# filter.net
KiCad netlist of a schematic drawn in EAGLE
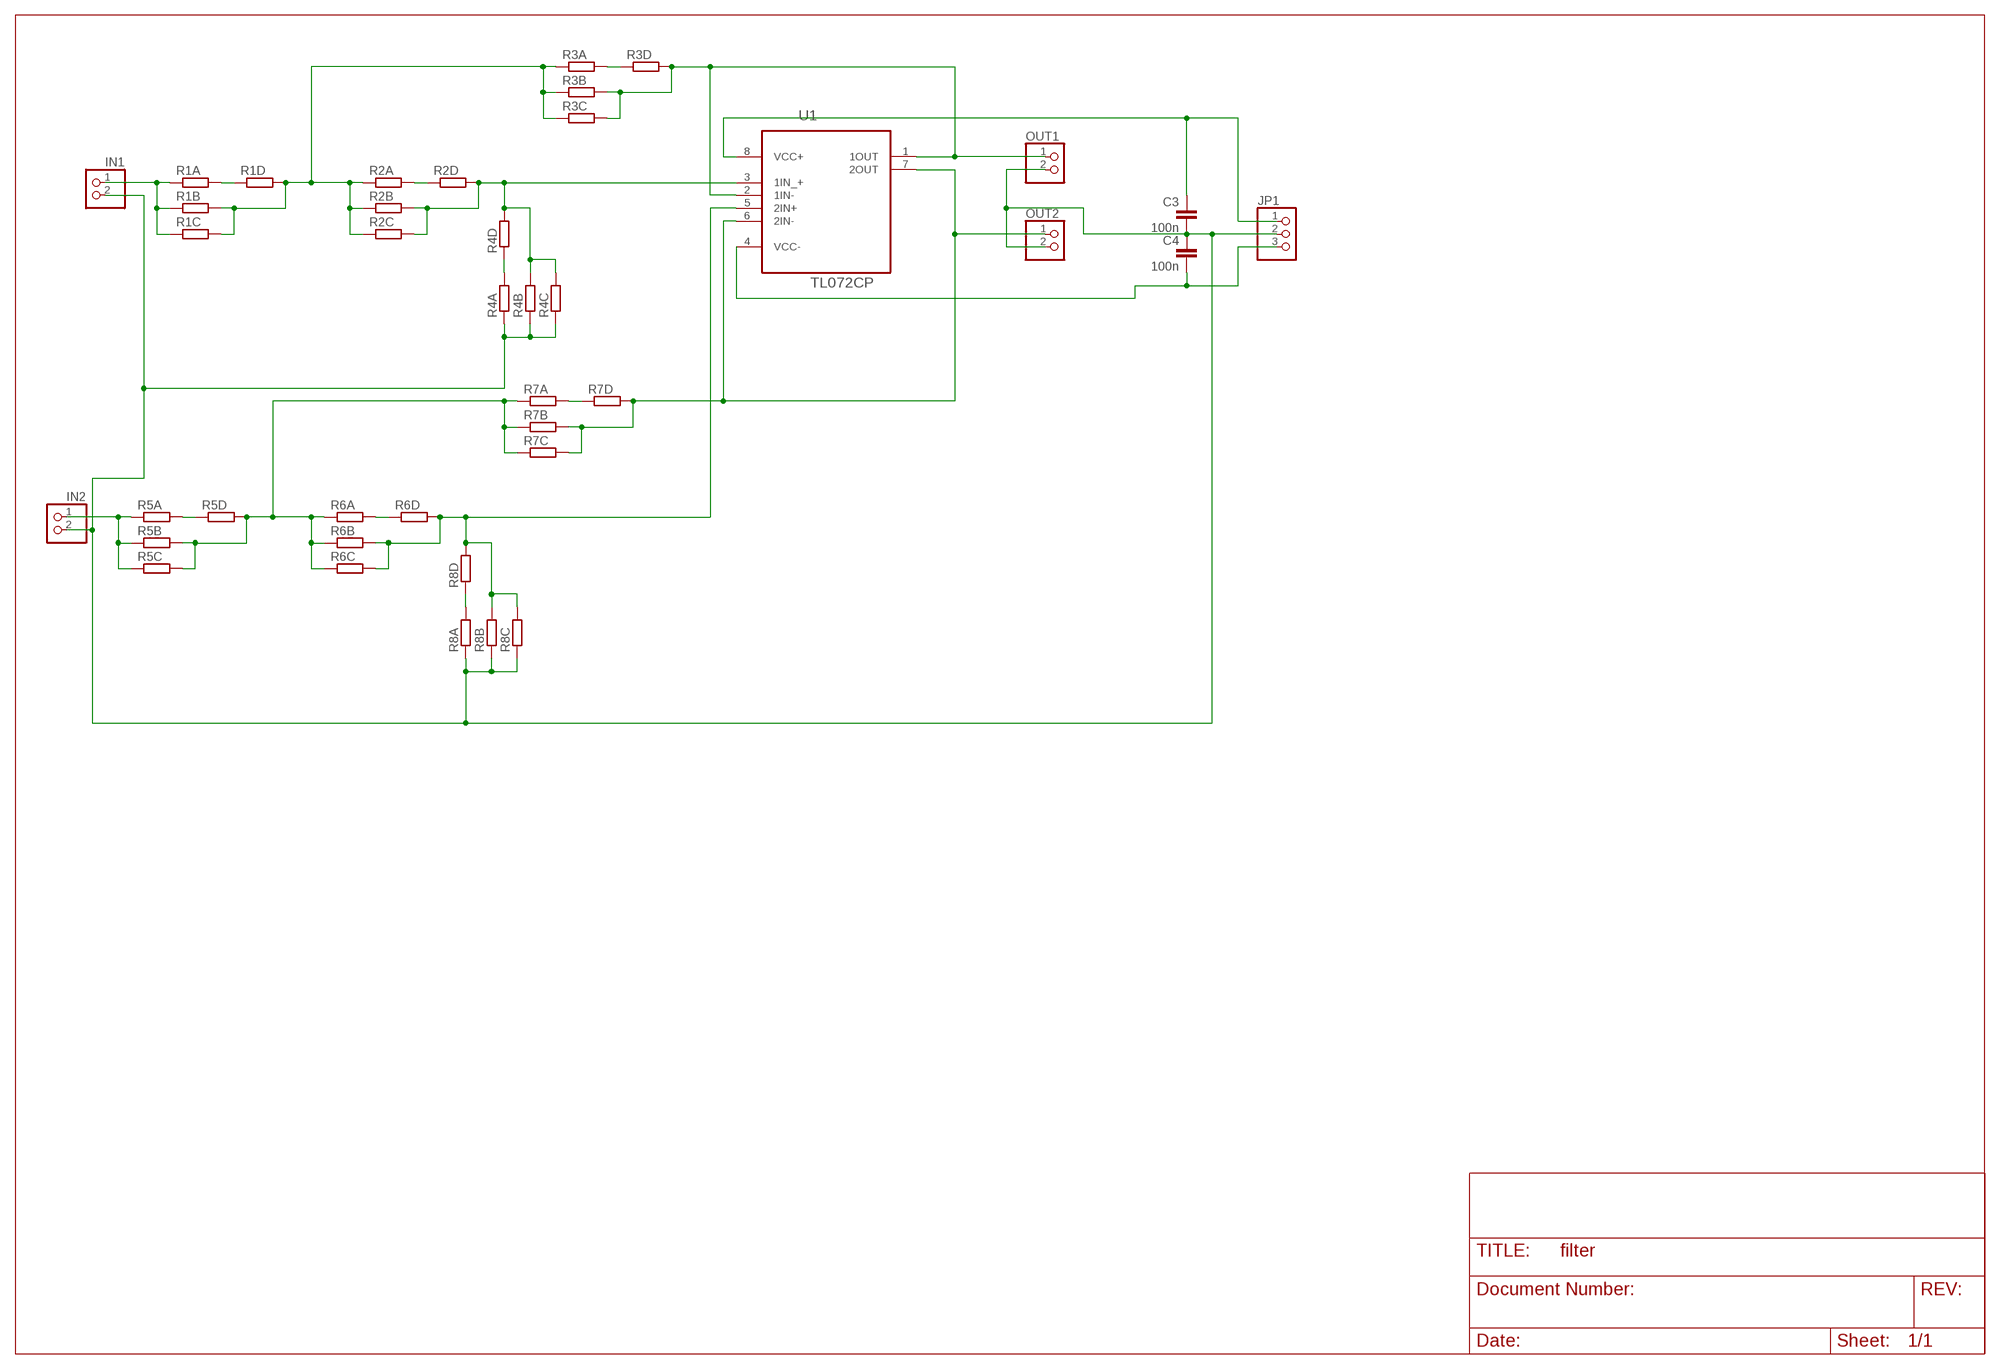
[diagram p0: schematic, sheet 1]

(export (version "E")
  (design (tool "Eeschema 10.0.6"))
  (components
    (comp (ref "C3")
      (value "100n")
      (footprint "eagle-import:C1206")
      (libsource (lib "eagle-import") (part "C-EUC1206"))
    )
    (comp (ref "C4")
      (value "100n")
      (footprint "eagle-import:C1206")
      (libsource (lib "eagle-import") (part "C-EUC1206"))
    )
    (comp (ref "IN1")
      (value "PINHD-1X2")
      (footprint "eagle-import:1X02")
      (libsource (lib "eagle-import") (part "PINHD-1X2"))
    )
    (comp (ref "IN2")
      (value "PINHD-1X2")
      (footprint "eagle-import:1X02")
      (libsource (lib "eagle-import") (part "PINHD-1X2"))
    )
    (comp (ref "JP1")
      (value "PINHD-1X3")
      (footprint "eagle-import:1X03")
      (libsource (lib "eagle-import") (part "PINHD-1X3"))
    )
    (comp (ref "OUT1")
      (value "PINHD-1X2")
      (footprint "eagle-import:1X02")
      (libsource (lib "eagle-import") (part "PINHD-1X2"))
    )
    (comp (ref "OUT2")
      (value "PINHD-1X2")
      (footprint "eagle-import:1X02")
      (libsource (lib "eagle-import") (part "PINHD-1X2"))
    )
    (comp (ref "R1A")
      (value "R-EU_0207/10")
      (footprint "eagle-import:0207_10")
      (libsource (lib "eagle-import") (part "R-EU_0207/10"))
    )
    (comp (ref "R1B")
      (value "R-EU_0207/10")
      (footprint "eagle-import:0207_10")
      (libsource (lib "eagle-import") (part "R-EU_0207/10"))
    )
    (comp (ref "R1C")
      (value "R-EU_0207/10")
      (footprint "eagle-import:0207_10")
      (libsource (lib "eagle-import") (part "R-EU_0207/10"))
    )
    (comp (ref "R1D")
      (value "R-EU_0207/10")
      (footprint "eagle-import:0207_10")
      (libsource (lib "eagle-import") (part "R-EU_0207/10"))
    )
    (comp (ref "R2A")
      (value "R-EU_0207/10")
      (footprint "eagle-import:0207_10")
      (libsource (lib "eagle-import") (part "R-EU_0207/10"))
    )
    (comp (ref "R2B")
      (value "R-EU_0207/10")
      (footprint "eagle-import:0207_10")
      (libsource (lib "eagle-import") (part "R-EU_0207/10"))
    )
    (comp (ref "R2C")
      (value "R-EU_0207/10")
      (footprint "eagle-import:0207_10")
      (libsource (lib "eagle-import") (part "R-EU_0207/10"))
    )
    (comp (ref "R2D")
      (value "R-EU_0207/10")
      (footprint "eagle-import:0207_10")
      (libsource (lib "eagle-import") (part "R-EU_0207/10"))
    )
    (comp (ref "R3A")
      (value "R-EU_0207/10")
      (footprint "eagle-import:0207_10")
      (libsource (lib "eagle-import") (part "R-EU_0207/10"))
    )
    (comp (ref "R3B")
      (value "R-EU_0207/10")
      (footprint "eagle-import:0207_10")
      (libsource (lib "eagle-import") (part "R-EU_0207/10"))
    )
    (comp (ref "R3C")
      (value "R-EU_0207/10")
      (footprint "eagle-import:0207_10")
      (libsource (lib "eagle-import") (part "R-EU_0207/10"))
    )
    (comp (ref "R3D")
      (value "R-EU_0207/10")
      (footprint "eagle-import:0207_10")
      (libsource (lib "eagle-import") (part "R-EU_0207/10"))
    )
    (comp (ref "R4A")
      (value "R-EU_0207/10")
      (footprint "eagle-import:0207_10")
      (libsource (lib "eagle-import") (part "R-EU_0207/10"))
    )
    (comp (ref "R4B")
      (value "R-EU_0207/10")
      (footprint "eagle-import:0207_10")
      (libsource (lib "eagle-import") (part "R-EU_0207/10"))
    )
    (comp (ref "R4C")
      (value "R-EU_0207/10")
      (footprint "eagle-import:0207_10")
      (libsource (lib "eagle-import") (part "R-EU_0207/10"))
    )
    (comp (ref "R4D")
      (value "R-EU_0207/10")
      (footprint "eagle-import:0207_10")
      (libsource (lib "eagle-import") (part "R-EU_0207/10"))
    )
    (comp (ref "R5A")
      (value "R-EU_0207/10")
      (footprint "eagle-import:0207_10")
      (libsource (lib "eagle-import") (part "R-EU_0207/10"))
    )
    (comp (ref "R5B")
      (value "R-EU_0207/10")
      (footprint "eagle-import:0207_10")
      (libsource (lib "eagle-import") (part "R-EU_0207/10"))
    )
    (comp (ref "R5C")
      (value "R-EU_0207/10")
      (footprint "eagle-import:0207_10")
      (libsource (lib "eagle-import") (part "R-EU_0207/10"))
    )
    (comp (ref "R5D")
      (value "R-EU_0207/10")
      (footprint "eagle-import:0207_10")
      (libsource (lib "eagle-import") (part "R-EU_0207/10"))
    )
    (comp (ref "R6A")
      (value "R-EU_0207/10")
      (footprint "eagle-import:0207_10")
      (libsource (lib "eagle-import") (part "R-EU_0207/10"))
    )
    (comp (ref "R6B")
      (value "R-EU_0207/10")
      (footprint "eagle-import:0207_10")
      (libsource (lib "eagle-import") (part "R-EU_0207/10"))
    )
    (comp (ref "R6C")
      (value "R-EU_0207/10")
      (footprint "eagle-import:0207_10")
      (libsource (lib "eagle-import") (part "R-EU_0207/10"))
    )
    (comp (ref "R6D")
      (value "R-EU_0207/10")
      (footprint "eagle-import:0207_10")
      (libsource (lib "eagle-import") (part "R-EU_0207/10"))
    )
    (comp (ref "R7A")
      (value "R-EU_0207/10")
      (footprint "eagle-import:0207_10")
      (libsource (lib "eagle-import") (part "R-EU_0207/10"))
    )
    (comp (ref "R7B")
      (value "R-EU_0207/10")
      (footprint "eagle-import:0207_10")
      (libsource (lib "eagle-import") (part "R-EU_0207/10"))
    )
    (comp (ref "R7C")
      (value "R-EU_0207/10")
      (footprint "eagle-import:0207_10")
      (libsource (lib "eagle-import") (part "R-EU_0207/10"))
    )
    (comp (ref "R7D")
      (value "R-EU_0207/10")
      (footprint "eagle-import:0207_10")
      (libsource (lib "eagle-import") (part "R-EU_0207/10"))
    )
    (comp (ref "R8A")
      (value "R-EU_0207/10")
      (footprint "eagle-import:0207_10")
      (libsource (lib "eagle-import") (part "R-EU_0207/10"))
    )
    (comp (ref "R8B")
      (value "R-EU_0207/10")
      (footprint "eagle-import:0207_10")
      (libsource (lib "eagle-import") (part "R-EU_0207/10"))
    )
    (comp (ref "R8C")
      (value "R-EU_0207/10")
      (footprint "eagle-import:0207_10")
      (libsource (lib "eagle-import") (part "R-EU_0207/10"))
    )
    (comp (ref "R8D")
      (value "R-EU_0207/10")
      (footprint "eagle-import:0207_10")
      (libsource (lib "eagle-import") (part "R-EU_0207/10"))
    )
    (comp (ref "U1")
      (value "TL072CP")
      (footprint "eagle-import:DIP254P762X508-8")
      (libsource (lib "eagle-import") (part "TL072CP"))
    )
  )
  (nets
    (net (code "1") (name "Net-(C3-Pad2)") (class "Default")
      (node (ref "C3") (pin "2") (pinfunction "2_2") (pintype "passive"))
      (node (ref "C4") (pin "1") (pinfunction "1_1") (pintype "passive"))
      (node (ref "IN1") (pin "2") (pinfunction "2_2") (pintype "passive"))
      (node (ref "IN2") (pin "2") (pinfunction "2_2") (pintype "passive"))
      (node (ref "JP1") (pin "2") (pinfunction "2_2") (pintype "passive"))
      (node (ref "OUT1") (pin "2") (pinfunction "2_2") (pintype "passive"))
      (node (ref "OUT2") (pin "2") (pinfunction "2_2") (pintype "passive"))
      (node (ref "R4A") (pin "1") (pinfunction "1_1") (pintype "passive"))
      (node (ref "R4B") (pin "1") (pinfunction "1_1") (pintype "passive"))
      (node (ref "R4C") (pin "1") (pinfunction "1_1") (pintype "passive"))
      (node (ref "R8A") (pin "1") (pinfunction "1_1") (pintype "passive"))
      (node (ref "R8B") (pin "1") (pinfunction "1_1") (pintype "passive"))
      (node (ref "R8C") (pin "1") (pinfunction "1_1") (pintype "passive"))
    )
    (net (code "2") (name "Net-(IN1-Pad1)") (class "Default")
      (node (ref "IN1") (pin "1") (pinfunction "1_1") (pintype "passive"))
      (node (ref "R1A") (pin "1") (pinfunction "1_1") (pintype "passive"))
      (node (ref "R1B") (pin "1") (pinfunction "1_1") (pintype "passive"))
      (node (ref "R1C") (pin "1") (pinfunction "1_1") (pintype "passive"))
    )
    (net (code "3") (name "Net-(IN2-Pad1)") (class "Default")
      (node (ref "IN2") (pin "1") (pinfunction "1_1") (pintype "passive"))
      (node (ref "R5A") (pin "1") (pinfunction "1_1") (pintype "passive"))
      (node (ref "R5B") (pin "1") (pinfunction "1_1") (pintype "passive"))
      (node (ref "R5C") (pin "1") (pinfunction "1_1") (pintype "passive"))
    )
    (net (code "4") (name "Net-(R1A-Pad2)") (class "Default")
      (node (ref "R1A") (pin "2") (pinfunction "2_2") (pintype "passive"))
      (node (ref "R1D") (pin "1") (pinfunction "1_1") (pintype "passive"))
    )
    (net (code "5") (name "Net-(R1B-Pad2)") (class "Default")
      (node (ref "R1B") (pin "2") (pinfunction "2_2") (pintype "passive"))
      (node (ref "R1C") (pin "2") (pinfunction "2_2") (pintype "passive"))
      (node (ref "R1D") (pin "2") (pinfunction "2_2") (pintype "passive"))
      (node (ref "R2A") (pin "1") (pinfunction "1_1") (pintype "passive"))
      (node (ref "R2B") (pin "1") (pinfunction "1_1") (pintype "passive"))
      (node (ref "R2C") (pin "1") (pinfunction "1_1") (pintype "passive"))
      (node (ref "R3A") (pin "1") (pinfunction "1_1") (pintype "passive"))
      (node (ref "R3B") (pin "1") (pinfunction "1_1") (pintype "passive"))
      (node (ref "R3C") (pin "1") (pinfunction "1_1") (pintype "passive"))
    )
    (net (code "6") (name "Net-(R2A-Pad2)") (class "Default")
      (node (ref "R2A") (pin "2") (pinfunction "2_2") (pintype "passive"))
      (node (ref "R2D") (pin "1") (pinfunction "1_1") (pintype "passive"))
    )
    (net (code "7") (name "Net-(R3A-Pad2)") (class "Default")
      (node (ref "R3A") (pin "2") (pinfunction "2_2") (pintype "passive"))
      (node (ref "R3D") (pin "1") (pinfunction "1_1") (pintype "passive"))
    )
    (net (code "8") (name "Net-(R4A-Pad2)") (class "Default")
      (node (ref "R4A") (pin "2") (pinfunction "2_2") (pintype "passive"))
      (node (ref "R4D") (pin "1") (pinfunction "1_1") (pintype "passive"))
    )
    (net (code "9") (name "Net-(R5A-Pad2)") (class "Default")
      (node (ref "R5A") (pin "2") (pinfunction "2_2") (pintype "passive"))
      (node (ref "R5D") (pin "1") (pinfunction "1_1") (pintype "passive"))
    )
    (net (code "10") (name "Net-(R5B-Pad2)") (class "Default")
      (node (ref "R5B") (pin "2") (pinfunction "2_2") (pintype "passive"))
      (node (ref "R5C") (pin "2") (pinfunction "2_2") (pintype "passive"))
      (node (ref "R5D") (pin "2") (pinfunction "2_2") (pintype "passive"))
      (node (ref "R6A") (pin "1") (pinfunction "1_1") (pintype "passive"))
      (node (ref "R6B") (pin "1") (pinfunction "1_1") (pintype "passive"))
      (node (ref "R6C") (pin "1") (pinfunction "1_1") (pintype "passive"))
      (node (ref "R7A") (pin "1") (pinfunction "1_1") (pintype "passive"))
      (node (ref "R7B") (pin "1") (pinfunction "1_1") (pintype "passive"))
      (node (ref "R7C") (pin "1") (pinfunction "1_1") (pintype "passive"))
    )
    (net (code "11") (name "Net-(R6A-Pad2)") (class "Default")
      (node (ref "R6A") (pin "2") (pinfunction "2_2") (pintype "passive"))
      (node (ref "R6D") (pin "1") (pinfunction "1_1") (pintype "passive"))
    )
    (net (code "12") (name "Net-(R7A-Pad2)") (class "Default")
      (node (ref "R7A") (pin "2") (pinfunction "2_2") (pintype "passive"))
      (node (ref "R7D") (pin "1") (pinfunction "1_1") (pintype "passive"))
    )
    (net (code "13") (name "Net-(R8A-Pad2)") (class "Default")
      (node (ref "R8A") (pin "2") (pinfunction "2_2") (pintype "passive"))
      (node (ref "R8D") (pin "1") (pinfunction "1_1") (pintype "passive"))
    )
    (net (code "14") (name "Net-(U1-1IN-)") (class "Default")
      (node (ref "OUT1") (pin "1") (pinfunction "1_1") (pintype "passive"))
      (node (ref "R3B") (pin "2") (pinfunction "2_2") (pintype "passive"))
      (node (ref "R3C") (pin "2") (pinfunction "2_2") (pintype "passive"))
      (node (ref "R3D") (pin "2") (pinfunction "2_2") (pintype "passive"))
      (node (ref "U1") (pin "1") (pinfunction "1OUT_1") (pintype "output"))
      (node (ref "U1") (pin "2") (pinfunction "1IN-_2") (pintype "input"))
    )
    (net (code "15") (name "Net-(U1-1IN_+)") (class "Default")
      (node (ref "R2B") (pin "2") (pinfunction "2_2") (pintype "passive"))
      (node (ref "R2C") (pin "2") (pinfunction "2_2") (pintype "passive"))
      (node (ref "R2D") (pin "2") (pinfunction "2_2") (pintype "passive"))
      (node (ref "R4B") (pin "2") (pinfunction "2_2") (pintype "passive"))
      (node (ref "R4C") (pin "2") (pinfunction "2_2") (pintype "passive"))
      (node (ref "R4D") (pin "2") (pinfunction "2_2") (pintype "passive"))
      (node (ref "U1") (pin "3") (pinfunction "1IN_+_3") (pintype "input"))
    )
    (net (code "16") (name "Net-(U1-2IN+)") (class "Default")
      (node (ref "R6B") (pin "2") (pinfunction "2_2") (pintype "passive"))
      (node (ref "R6C") (pin "2") (pinfunction "2_2") (pintype "passive"))
      (node (ref "R6D") (pin "2") (pinfunction "2_2") (pintype "passive"))
      (node (ref "R8B") (pin "2") (pinfunction "2_2") (pintype "passive"))
      (node (ref "R8C") (pin "2") (pinfunction "2_2") (pintype "passive"))
      (node (ref "R8D") (pin "2") (pinfunction "2_2") (pintype "passive"))
      (node (ref "U1") (pin "5") (pinfunction "2IN+_5") (pintype "input"))
    )
    (net (code "17") (name "Net-(U1-2IN-)") (class "Default")
      (node (ref "OUT2") (pin "1") (pinfunction "1_1") (pintype "passive"))
      (node (ref "R7B") (pin "2") (pinfunction "2_2") (pintype "passive"))
      (node (ref "R7C") (pin "2") (pinfunction "2_2") (pintype "passive"))
      (node (ref "R7D") (pin "2") (pinfunction "2_2") (pintype "passive"))
      (node (ref "U1") (pin "6") (pinfunction "2IN-_6") (pintype "input"))
      (node (ref "U1") (pin "7") (pinfunction "2OUT_7") (pintype "output"))
    )
    (net (code "18") (name "Net-(U1-VCC+)") (class "Default")
      (node (ref "C3") (pin "1") (pinfunction "1_1") (pintype "passive"))
      (node (ref "JP1") (pin "1") (pinfunction "1_1") (pintype "passive"))
      (node (ref "U1") (pin "8") (pinfunction "VCC+_8") (pintype "power_in"))
    )
    (net (code "19") (name "Net-(U1-VCC-)") (class "Default")
      (node (ref "C4") (pin "2") (pinfunction "2_2") (pintype "passive"))
      (node (ref "JP1") (pin "3") (pinfunction "3_3") (pintype "passive"))
      (node (ref "U1") (pin "4") (pinfunction "VCC-_4") (pintype "passive"))
    )
  )
)
